# mini2.net
KiCad netlist of a schematic drawn in EasyEDA Pro
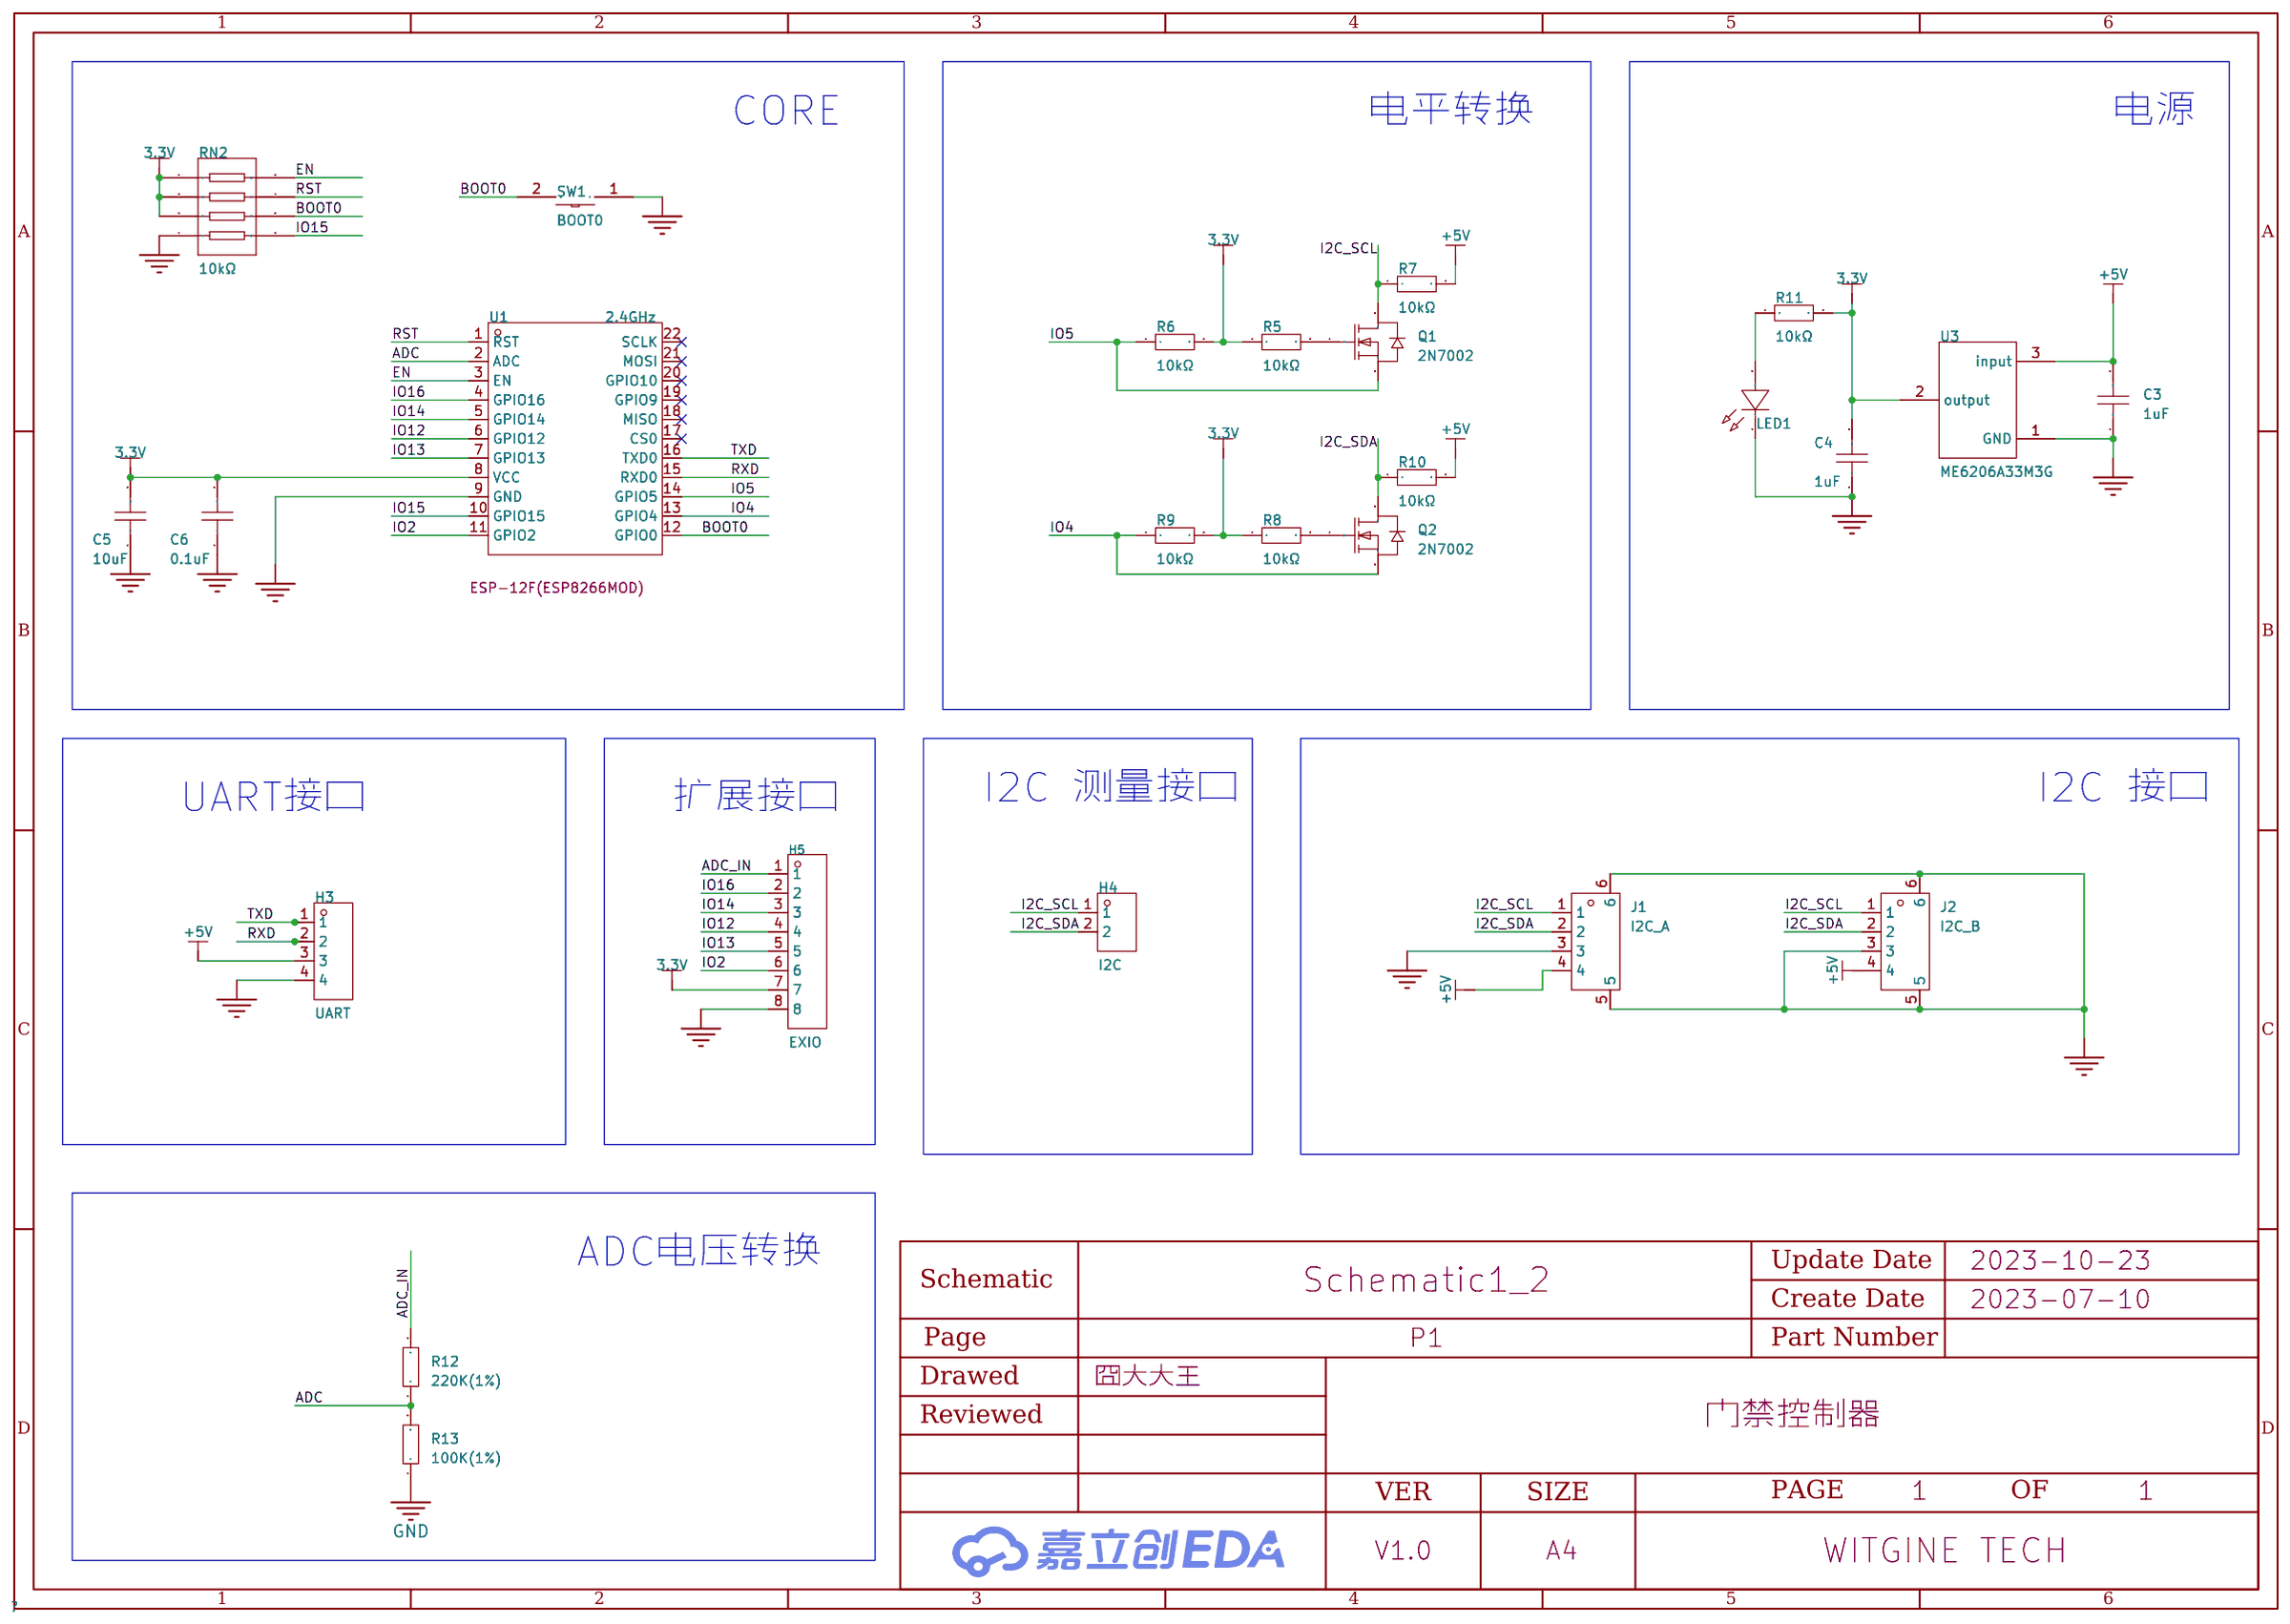
[diagram p0: schematic sheet]

(export (version "E")
  (design (tool "Eeschema 10.0.6"))
  (components
    (comp (ref "C3")
      (value "1uF")
      (fields
        (field (name "Manufacturer Part") "CL10A106MA8NRNC")
        (field (name "Manufacturer") "SAMSUNG(三星)")
      )
      (libsource (lib "easyedapro") (part "CapAcitance"))
    )
    (comp (ref "C4")
      (value "1uF")
      (fields
        (field (name "Manufacturer Part") "CL10B104KB8NNNC")
        (field (name "Manufacturer") "SAMSUNG(三星)")
      )
      (libsource (lib "easyedapro") (part "CapAcitance"))
    )
    (comp (ref "C5")
      (value "10uF")
      (fields
        (field (name "Manufacturer Part") "CL10A106MA8NRNC")
        (field (name "Manufacturer") "SAMSUNG(三星)")
        (field (name "Supplier Part") "C96446")
      )
      (libsource (lib "easyedapro") (part "CapAcitance"))
    )
    (comp (ref "C6")
      (value "0.1uF")
      (fields
        (field (name "Manufacturer Part") "CL10B104KB8NNNC")
        (field (name "Manufacturer") "SAMSUNG(三星)")
      )
      (libsource (lib "easyedapro") (part "CapAcitance"))
    )
    (comp (ref "H3")
      (value "UART")
      (fields (field (name "Manufacturer Part") "PZ254V-11-04P") (field (name "Manufacturer") "XFCN(兴飞)"))
      (libsource (lib "easyedapro") (part "PZ254V-11-04P_C2691448"))
    )
    (comp (ref "H4")
      (value "I2C")
      (footprint "easyedapro:HDR-TH_2P-P2.54-V-M")
      (fields (field (name "Manufacturer Part") "2.54-1x2P直针") (field (name "Manufacturer") "XFCN(兴飞)"))
      (libsource (lib "easyedapro") (part "PZ254V-11-02P"))
    )
    (comp (ref "H5")
      (value "EXIO")
      (footprint "easyedapro:HDR-TH_8P-P2.54-V-M")
      (fields (field (name "Manufacturer Part") "PZ254V-11-08P") (field (name "Manufacturer") "XFCN(兴飞)"))
      (libsource (lib "easyedapro") (part "PZ254V-11-08P"))
    )
    (comp (ref "J1")
      (value "I2C_A")
      (footprint "easyedapro:CONN-SMD_1.25-4PWB")
      (description "参考系列:-;间距:1.25mm;插针结构:1x4P;排数:1;每排PIN数:4;行距:-;公母:公型插针;安装方式:卧贴;额定电流:-;工作温度范围:-40°C~+85°C;")
      (fields (field (name "Manufacturer Part") "1.25-4PWB") (field (name "Manufacturer") "DEALON(德艺隆)"))
      (libsource (lib "easyedapro") (part "1.25-4PWB"))
    )
    (comp (ref "J2")
      (value "I2C_B")
      (footprint "easyedapro:CONN-SMD_1.25-4PWB")
      (description "参考系列:-;间距:1.25mm;插针结构:1x4P;排数:1;每排PIN数:4;行距:-;公母:公型插针;安装方式:卧贴;额定电流:-;工作温度范围:-40°C~+85°C;")
      (fields (field (name "Manufacturer Part") "1.25-4PWB") (field (name "Manufacturer") "DEALON(德艺隆)"))
      (libsource (lib "easyedapro") (part "1.25-4PWB"))
    )
    (comp (ref "LED1")
      (value "XL-1608SURC-06")
      (footprint "easyedapro:LED0603-RD_RED")
      (description "发光颜色:红灯;主波长:617nm~621nm;色温:-;功率:55mW;安装方式:正贴;")
      (fields (field (name "Manufacturer") "XINGLIGHT(成兴光)"))
      (libsource (lib "easyedapro") (part "XL-1608SURC-06"))
    )
    (comp (ref "Q1")
      (value "2N7002")
      (footprint "easyedapro:SOT-23-3_L2.9-W1.3-P1.90-LS2.4-BR")
      (fields (field (name "Manufacturer") "CJ(江苏长电/长晶)"))
      (libsource (lib "easyedapro") (part "2N7002"))
    )
    (comp (ref "Q2")
      (value "2N7002")
      (footprint "easyedapro:SOT-23-3_L2.9-W1.3-P1.90-LS2.4-BR")
      (fields (field (name "Manufacturer") "CJ(江苏长电/长晶)"))
      (libsource (lib "easyedapro") (part "2N7002"))
    )
    (comp (ref "R5")
      (value "10kΩ")
      (footprint "easyedapro:R0603")
      (fields (field (name "Manufacturer Part") "RS-03K1002FT") (field (name "Manufacturer") "FH(风华)"))
      (libsource (lib "easyedapro") (part "电阻"))
    )
    (comp (ref "R6")
      (value "10kΩ")
      (footprint "easyedapro:R0603")
      (fields (field (name "Manufacturer Part") "RS-03K1002FT") (field (name "Manufacturer") "FH(风华)"))
      (libsource (lib "easyedapro") (part "电阻"))
    )
    (comp (ref "R7")
      (value "10kΩ")
      (footprint "easyedapro:R0603")
      (fields (field (name "Manufacturer Part") "RS-03K1002FT") (field (name "Manufacturer") "FH(风华)"))
      (libsource (lib "easyedapro") (part "电阻"))
    )
    (comp (ref "R8")
      (value "10kΩ")
      (footprint "easyedapro:R0603")
      (fields (field (name "Manufacturer Part") "RS-03K1002FT") (field (name "Manufacturer") "FH(风华)"))
      (libsource (lib "easyedapro") (part "电阻"))
    )
    (comp (ref "R9")
      (value "10kΩ")
      (footprint "easyedapro:R0603")
      (fields (field (name "Manufacturer Part") "RS-03K1002FT") (field (name "Manufacturer") "FH(风华)"))
      (libsource (lib "easyedapro") (part "电阻"))
    )
    (comp (ref "R10")
      (value "10kΩ")
      (footprint "easyedapro:R0603")
      (fields (field (name "Manufacturer Part") "RS-03K1002FT") (field (name "Manufacturer") "FH(风华)"))
      (libsource (lib "easyedapro") (part "电阻"))
    )
    (comp (ref "R11")
      (value "10kΩ")
      (footprint "easyedapro:R0603")
      (libsource (lib "easyedapro") (part "电阻"))
    )
    (comp (ref "R12")
      (value "220K(1%)")
      (footprint "easyedapro:R0603")
      (libsource (lib "easyedapro") (part "电阻"))
    )
    (comp (ref "R13")
      (value "100K(1%)")
      (footprint "easyedapro:R0603")
      (libsource (lib "easyedapro") (part "电阻"))
    )
    (comp (ref "RN2")
      (value "10kΩ")
      (footprint "easyedapro:RES-ARRAY-SMD_0603-8P-L3.2-W1.6-BL")
      (description "阻值:10kΩ;精度:±5%;单个元件功率:62.5mW;电阻器数:4;")
      (fields
        (field (name "Manufacturer Part") "4D03WGJ0103T5E")
        (field (name "Manufacturer") "UNI-ROYAL(厚声)")
      )
      (libsource (lib "easyedapro") (part "4D03WGJ0103T5E"))
    )
    (comp (ref "SW1")
      (value "BOOT0")
      (fields (field (name "Manufacturer Part") "TS-1088-AR02016") (field (name "Manufacturer") "XUNPU(讯普)"))
      (libsource (lib "easyedapro") (part "TS-1101-C-W"))
    )
    (comp (ref "U1")
      (value "2.4GHz")
      (footprint "easyedapro:WIFIM-SMD_ESP-12F-ESP8266MOD")
      (description "频率:2.4GHz;发射功率:16dBm;核心处理器:ESP8266;天线形式:PCB 板载天线;接收灵敏度:-90dBm;")
      (fields
        (field (name "Manufacturer Part") "ESP-12F(ESP8266MOD)")
        (field (name "Manufacturer") "Ai-Thinker(安信可)")
      )
      (libsource (lib "easyedapro") (part "ESP-12F(ESP8266MOD)"))
    )
    (comp (ref "U3")
      (value "ME6206A33M3G")
      (footprint "easyedapro:SOT-23-3_L2.9-W1.6-P1.90-LS2.8-BR")
      (description "输出类型:固定;输出极性:正;最大输入电压:6V;输出电压:3.3V;输出电流:300mA;电源纹波抑制比(PSRR):50dB@(1kHz);")
      (fields (field (name "Manufacturer") "MICRONE(南京微盟)"))
      (libsource (lib "easyedapro") (part "ME6206A33M3G"))
    )
  )
  (nets
    (net (code "1") (name "+5V") (class "Default")
      (node (ref "C3") (pin "2") (pinfunction "2_2") (pintype "input"))
      (node (ref "H3") (pin "3") (pinfunction "3_3") (pintype "input"))
      (node (ref "J1") (pin "4") (pinfunction "4_4") (pintype "input"))
      (node (ref "J2") (pin "4") (pinfunction "4_4") (pintype "input"))
      (node (ref "R10") (pin "2") (pinfunction "2_2") (pintype "input"))
      (node (ref "R7") (pin "2") (pinfunction "2_2") (pintype "input"))
      (node (ref "U3") (pin "3") (pinfunction "input_3") (pintype "input"))
    )
    (net (code "2") (name "/ADC") (class "Default")
      (node (ref "R12") (pin "1") (pinfunction "1_1") (pintype "input"))
      (node (ref "R13") (pin "2") (pinfunction "2_2") (pintype "input"))
      (node (ref "U1") (pin "2") (pinfunction "ADC_2") (pintype "input"))
    )
    (net (code "3") (name "/ADC_IN") (class "Default")
      (node (ref "H5") (pin "1") (pinfunction "1_1") (pintype "input"))
      (node (ref "R12") (pin "2") (pinfunction "2_2") (pintype "input"))
    )
    (net (code "4") (name "/BOOT0") (class "Default")
      (node (ref "RN2") (pin "6") (pinfunction "6_6") (pintype "input"))
      (node (ref "SW1") (pin "2") (pinfunction "2_2") (pintype "input"))
      (node (ref "U1") (pin "12") (pinfunction "GPIO0_12") (pintype "input"))
    )
    (net (code "5") (name "/EN") (class "Default")
      (node (ref "RN2") (pin "8") (pinfunction "8_8") (pintype "input"))
      (node (ref "U1") (pin "3") (pinfunction "EN_3") (pintype "input"))
    )
    (net (code "6") (name "/I2C_SCL") (class "Default")
      (node (ref "H4") (pin "1") (pinfunction "1_1") (pintype "input"))
      (node (ref "J1") (pin "1") (pinfunction "1_1") (pintype "input"))
      (node (ref "J2") (pin "1") (pinfunction "1_1") (pintype "input"))
      (node (ref "Q1") (pin "3") (pinfunction "D_3") (pintype "input"))
      (node (ref "R7") (pin "1") (pinfunction "1_1") (pintype "input"))
    )
    (net (code "7") (name "/I2C_SDA") (class "Default")
      (node (ref "H4") (pin "2") (pinfunction "2_2") (pintype "input"))
      (node (ref "J1") (pin "2") (pinfunction "2_2") (pintype "input"))
      (node (ref "J2") (pin "2") (pinfunction "2_2") (pintype "input"))
      (node (ref "Q2") (pin "3") (pinfunction "D_3") (pintype "input"))
      (node (ref "R10") (pin "1") (pinfunction "1_1") (pintype "input"))
    )
    (net (code "8") (name "/IO2") (class "Default")
      (node (ref "H5") (pin "6") (pinfunction "6_6") (pintype "input"))
      (node (ref "U1") (pin "11") (pinfunction "GPIO2_11") (pintype "input"))
    )
    (net (code "9") (name "/IO4") (class "Default")
      (node (ref "Q2") (pin "2") (pinfunction "S_2") (pintype "input"))
      (node (ref "R9") (pin "1") (pinfunction "1_1") (pintype "input"))
      (node (ref "U1") (pin "13") (pinfunction "GPIO4_13") (pintype "input"))
    )
    (net (code "10") (name "/IO5") (class "Default")
      (node (ref "Q1") (pin "2") (pinfunction "S_2") (pintype "input"))
      (node (ref "R6") (pin "1") (pinfunction "1_1") (pintype "input"))
      (node (ref "U1") (pin "14") (pinfunction "GPIO5_14") (pintype "input"))
    )
    (net (code "11") (name "/IO12") (class "Default")
      (node (ref "H5") (pin "4") (pinfunction "4_4") (pintype "input"))
      (node (ref "U1") (pin "6") (pinfunction "GPIO12_6") (pintype "input"))
    )
    (net (code "12") (name "/IO13") (class "Default")
      (node (ref "H5") (pin "5") (pinfunction "5_5") (pintype "input"))
      (node (ref "U1") (pin "7") (pinfunction "GPIO13_7") (pintype "input"))
    )
    (net (code "13") (name "/IO14") (class "Default")
      (node (ref "H5") (pin "3") (pinfunction "3_3") (pintype "input"))
      (node (ref "U1") (pin "5") (pinfunction "GPIO14_5") (pintype "input"))
    )
    (net (code "14") (name "/IO15") (class "Default")
      (node (ref "RN2") (pin "5") (pinfunction "5_5") (pintype "input"))
      (node (ref "U1") (pin "10") (pinfunction "GPIO15_10") (pintype "input"))
    )
    (net (code "15") (name "/IO16") (class "Default")
      (node (ref "H5") (pin "2") (pinfunction "2_2") (pintype "input"))
      (node (ref "U1") (pin "4") (pinfunction "GPIO16_4") (pintype "input"))
    )
    (net (code "16") (name "/RST") (class "Default")
      (node (ref "RN2") (pin "7") (pinfunction "7_7") (pintype "input"))
      (node (ref "U1") (pin "1") (pinfunction "RST_1") (pintype "input"))
    )
    (net (code "17") (name "/RXD") (class "Default")
      (node (ref "H3") (pin "2") (pinfunction "2_2") (pintype "input"))
      (node (ref "U1") (pin "15") (pinfunction "RXD0_15") (pintype "input"))
    )
    (net (code "18") (name "/TXD") (class "Default")
      (node (ref "H3") (pin "1") (pinfunction "1_1") (pintype "input"))
      (node (ref "U1") (pin "16") (pinfunction "TXD0_16") (pintype "input"))
    )
    (net (code "19") (name "3.3V") (class "Default")
      (node (ref "C4") (pin "2") (pinfunction "2_2") (pintype "input"))
      (node (ref "C5") (pin "2") (pinfunction "2_2") (pintype "input"))
      (node (ref "C6") (pin "2") (pinfunction "2_2") (pintype "input"))
      (node (ref "H5") (pin "7") (pinfunction "7_7") (pintype "input"))
      (node (ref "R11") (pin "2") (pinfunction "2_2") (pintype "input"))
      (node (ref "R5") (pin "1") (pinfunction "1_1") (pintype "input"))
      (node (ref "R6") (pin "2") (pinfunction "2_2") (pintype "input"))
      (node (ref "R8") (pin "1") (pinfunction "1_1") (pintype "input"))
      (node (ref "R9") (pin "2") (pinfunction "2_2") (pintype "input"))
      (node (ref "RN2") (pin "1") (pinfunction "1_1") (pintype "input"))
      (node (ref "RN2") (pin "2") (pinfunction "2_2") (pintype "input"))
      (node (ref "RN2") (pin "3") (pinfunction "3_3") (pintype "input"))
      (node (ref "U1") (pin "8") (pinfunction "VCC_8") (pintype "input"))
      (node (ref "U3") (pin "2") (pinfunction "output_2") (pintype "input"))
    )
    (net (code "20") (name "GND") (class "Default")
      (node (ref "C3") (pin "1") (pinfunction "1_1") (pintype "input"))
      (node (ref "C4") (pin "1") (pinfunction "1_1") (pintype "input"))
      (node (ref "C5") (pin "1") (pinfunction "1_1") (pintype "input"))
      (node (ref "C6") (pin "1") (pinfunction "1_1") (pintype "input"))
      (node (ref "H3") (pin "4") (pinfunction "4_4") (pintype "input"))
      (node (ref "H5") (pin "8") (pinfunction "8_8") (pintype "input"))
      (node (ref "J1") (pin "3") (pinfunction "3_3") (pintype "input"))
      (node (ref "J1") (pin "5") (pinfunction "5_5") (pintype "input"))
      (node (ref "J1") (pin "6") (pinfunction "6_6") (pintype "input"))
      (node (ref "J2") (pin "3") (pinfunction "3_3") (pintype "input"))
      (node (ref "J2") (pin "5") (pinfunction "5_5") (pintype "input"))
      (node (ref "J2") (pin "6") (pinfunction "6_6") (pintype "input"))
      (node (ref "LED1") (pin "1") (pinfunction "K_1") (pintype "input"))
      (node (ref "R13") (pin "1") (pinfunction "1_1") (pintype "input"))
      (node (ref "RN2") (pin "4") (pinfunction "4_4") (pintype "input"))
      (node (ref "SW1") (pin "1") (pinfunction "1_1") (pintype "input"))
      (node (ref "U1") (pin "9") (pinfunction "GND_9") (pintype "input"))
      (node (ref "U3") (pin "1") (pinfunction "GND_1") (pintype "input"))
    )
    (net (code "21") (name "Net-(LED1-A)") (class "Default")
      (node (ref "LED1") (pin "2") (pinfunction "A_2") (pintype "input"))
      (node (ref "R11") (pin "1") (pinfunction "1_1") (pintype "input"))
    )
    (net (code "22") (name "Net-(Q1-G)") (class "Default")
      (node (ref "Q1") (pin "1") (pinfunction "G_1") (pintype "input"))
      (node (ref "R5") (pin "2") (pinfunction "2_2") (pintype "input"))
    )
    (net (code "23") (name "Net-(Q2-G)") (class "Default")
      (node (ref "Q2") (pin "1") (pinfunction "G_1") (pintype "input"))
      (node (ref "R8") (pin "2") (pinfunction "2_2") (pintype "input"))
    )
    (net (code "24") (name "unconnected-(U1-CS0-Pad17)") (class "Default")
      (node (ref "U1") (pin "17") (pinfunction "CS0_17") (pintype "input+no_connect"))
    )
    (net (code "25") (name "unconnected-(U1-GPIO9-Pad19)") (class "Default")
      (node (ref "U1") (pin "19") (pinfunction "GPIO9_19") (pintype "input+no_connect"))
    )
    (net (code "26") (name "unconnected-(U1-GPIO10-Pad20)") (class "Default")
      (node (ref "U1") (pin "20") (pinfunction "GPIO10_20") (pintype "input+no_connect"))
    )
    (net (code "27") (name "unconnected-(U1-MISO-Pad18)") (class "Default")
      (node (ref "U1") (pin "18") (pinfunction "MISO_18") (pintype "input+no_connect"))
    )
    (net (code "28") (name "unconnected-(U1-MOSI-Pad21)") (class "Default")
      (node (ref "U1") (pin "21") (pinfunction "MOSI_21") (pintype "input+no_connect"))
    )
    (net (code "29") (name "unconnected-(U1-SCLK-Pad22)") (class "Default")
      (node (ref "U1") (pin "22") (pinfunction "SCLK_22") (pintype "input+no_connect"))
    )
  )
)
